# Slave.net
KiCad netlist of a schematic drawn in Altium Designer
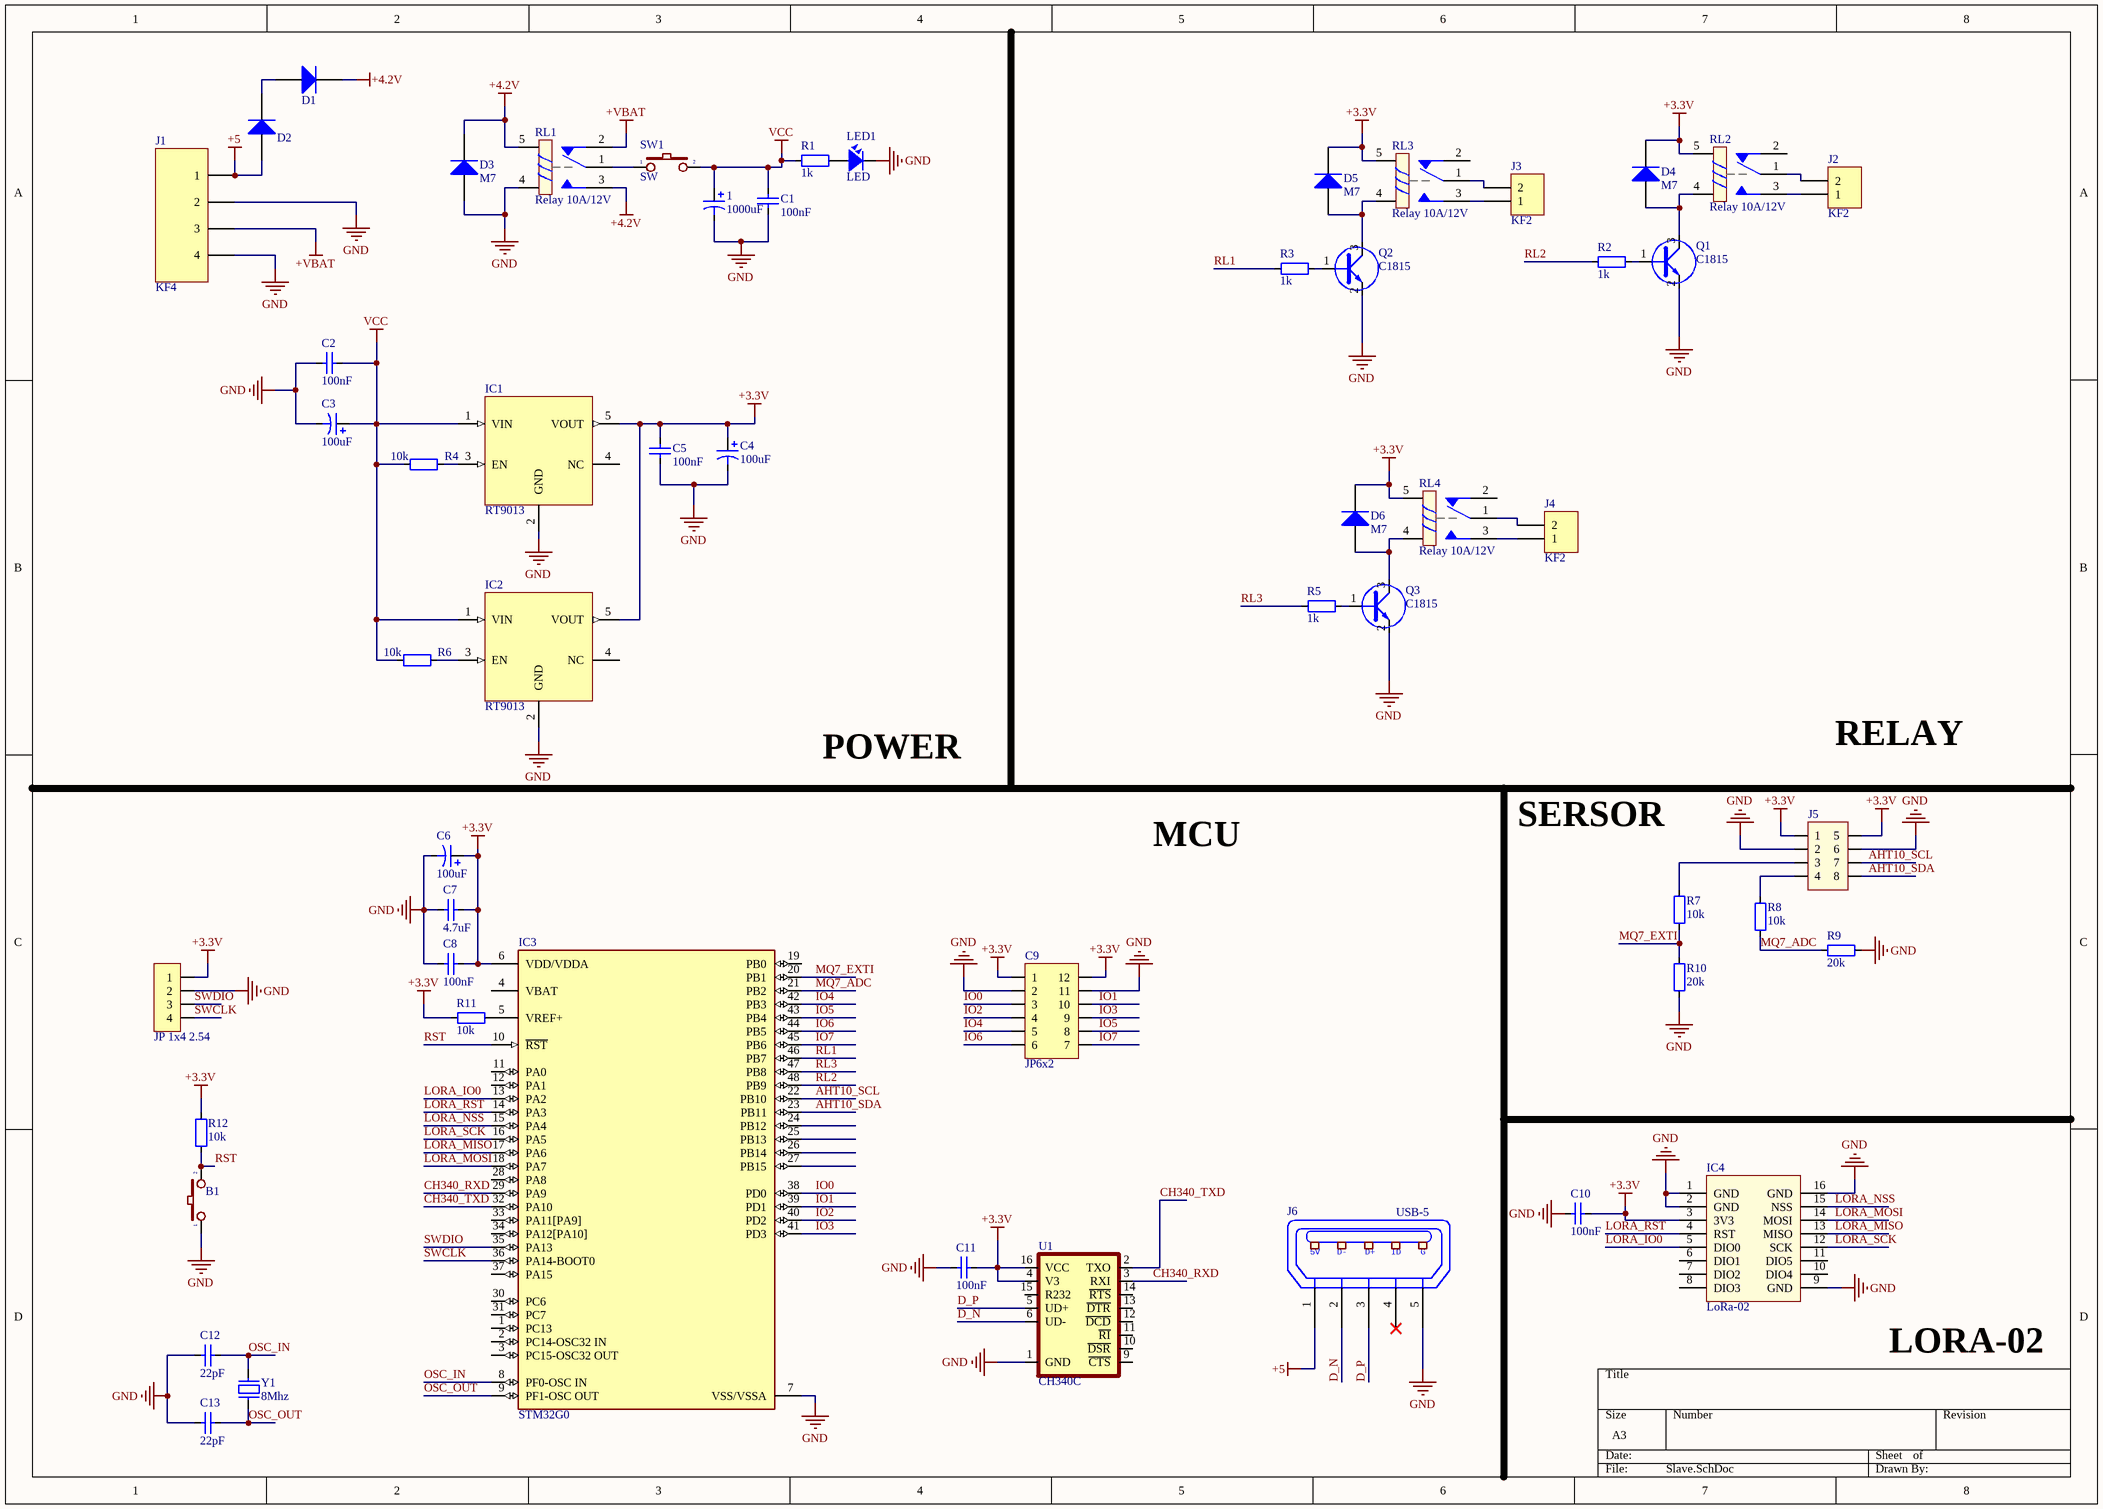
[diagram p0: Slave.SchDoc]

(export (version "E")
  (design (tool "Eeschema 10.0.6"))
  (components
    (comp (ref "1")
      (value "1000uF")
      (footprint "C8mm")
      (description "1000uF 16V 8x16mm")
      (fields (field (name "PUBLISHER") "Altium Limited"))
      (libsource (lib "My Library") (part "Cap Pol"))
    )
    (comp (ref "B1")
      (value "Button 3x4x2.5")
      (footprint "Button 3x4x2.5")
      (libsource (lib "My Library") (part "Button 3x4x2.5"))
    )
    (comp (ref "C1")
      (value "100nF")
      (footprint "CAP_0805")
      (description "Capacitor")
      (fields (field (name "PUBLISHER") "Altium Limited"))
      (libsource (lib "My Library") (part "CapSMD"))
    )
    (comp (ref "C2")
      (value "100nF")
      (footprint "CAP_0805")
      (description "Capacitor")
      (fields (field (name "PUBLISHER") "Altium Limited"))
      (libsource (lib "My Library") (part "CapSMD"))
    )
    (comp (ref "C3")
      (value "100uF")
      (footprint "C5mm")
      (description "100uF 16V")
      (fields (field (name "PUBLISHER") "Altium Limited"))
      (libsource (lib "My Library") (part "Cap Pol"))
    )
    (comp (ref "C4")
      (value "100uF")
      (footprint "C5mm")
      (description "100uF 16V")
      (fields (field (name "PUBLISHER") "Altium Limited"))
      (libsource (lib "My Library") (part "Cap Pol"))
    )
    (comp (ref "C5")
      (value "100nF")
      (footprint "CAP_0805")
      (description "Capacitor")
      (fields (field (name "PUBLISHER") "Altium Limited"))
      (libsource (lib "My Library") (part "CapSMD"))
    )
    (comp (ref "C6")
      (value "100uF")
      (footprint "C5mm")
      (description "100uF 16V")
      (fields (field (name "PUBLISHER") "Altium Limited"))
      (libsource (lib "My Library") (part "Cap Pol"))
    )
    (comp (ref "C7")
      (value "4.7uF")
      (footprint "CAP_0805")
      (description "Capacitor")
      (fields (field (name "PUBLISHER") "Altium Limited"))
      (libsource (lib "My Library") (part "CapSMD"))
    )
    (comp (ref "C8")
      (value "100nF")
      (footprint "CAP_0805")
      (description "Capacitor")
      (fields (field (name "PUBLISHER") "Altium Limited"))
      (libsource (lib "My Library") (part "CapSMD"))
    )
    (comp (ref "C9")
      (value "JP6x2")
      (footprint "JP6-D2T")
      (description "WR-PHD 2.54 mm Dual Socket Header")
      (fields
        (field (name "MANUFACTURER") "Würth Elektronik eiSos GmbH")
        (field (name "PARTNO") "61301221821")
        (field (name "CREATED BY") "Karrer Zheng")
      )
      (libsource (lib "My Library") (part "JP6x2"))
    )
    (comp (ref "C10")
      (value "100nF")
      (footprint "CAP_0805")
      (description "Capacitor")
      (fields (field (name "PUBLISHER") "Altium Limited"))
      (libsource (lib "My Library") (part "CapSMD"))
    )
    (comp (ref "C11")
      (value "100nF")
      (footprint "CAP_0805")
      (description "Capacitor")
      (fields (field (name "PUBLISHER") "Altium Limited"))
      (libsource (lib "My Library") (part "CapSMD"))
    )
    (comp (ref "C12")
      (value "22pF")
      (footprint "CAP_0805")
      (description "Capacitor")
      (fields (field (name "PUBLISHER") "Altium Limited"))
      (libsource (lib "My Library") (part "CapSMD"))
    )
    (comp (ref "C13")
      (value "22pF")
      (footprint "CAP_0805")
      (description "Capacitor")
      (fields (field (name "PUBLISHER") "Altium Limited"))
      (libsource (lib "My Library") (part "CapSMD"))
    )
    (comp (ref "D1")
      (value "SS34 Diode 3A 40V")
      (footprint "DIODE SMA")
      (description "Dán")
      (libsource (lib "Altium_Lib_by_KhueNguyenCreator") (part "Diode M7 ( 4007 )"))
    )
    (comp (ref "D2")
      (value "SS34 Diode 3A 40V")
      (footprint "DIODE SMA")
      (description "Dán")
      (libsource (lib "Altium_Lib_by_KhueNguyenCreator") (part "Diode M7 ( 4007 )"))
    )
    (comp (ref "D3")
      (value "M7")
      (footprint "DIODE SMA")
      (description "Dán")
      (libsource (lib "Altium_Lib_by_KhueNguyenCreator") (part "Diode M7 ( 4007 )"))
    )
    (comp (ref "D4")
      (value "M7")
      (footprint "DIODE SMA")
      (description "Dán")
      (libsource (lib "Altium_Lib_by_KhueNguyenCreator") (part "Diode M7 ( 4007 )"))
    )
    (comp (ref "D5")
      (value "M7")
      (footprint "DIODE SMA")
      (description "Dán")
      (libsource (lib "Altium_Lib_by_KhueNguyenCreator") (part "Diode M7 ( 4007 )"))
    )
    (comp (ref "D6")
      (value "M7")
      (footprint "DIODE SMA")
      (description "Dán")
      (libsource (lib "Altium_Lib_by_KhueNguyenCreator") (part "Diode M7 ( 4007 )"))
    )
    (comp (ref "IC1")
      (value "RT9013")
      (footprint "SOT23-5")
      (description "RT9013-33GB IC REG LINEAR 3.3V 500mA SOT23-5")
      (libsource (lib "My Library") (part "RT9013"))
    )
    (comp (ref "IC2")
      (value "RT9013")
      (footprint "SOT23-5")
      (description "RT9013-33GB IC REG LINEAR 3.3V 500mA SOT23-5")
      (libsource (lib "My Library") (part "RT9013"))
    )
    (comp (ref "IC3") (value "STM32G0") (footprint "STM32G0") (libsource (lib "My Library") (part "STM32G0")))
    (comp (ref "IC4") (value "LoRa-02") (footprint "LoRa-02") (libsource (lib "My Library") (part "LoRa-02")))
    (comp (ref "J1")
      (value "KF4")
      (footprint "KF4-5.08")
      (fields
        (field (name "MANUFACTURER") "Würth Elektronik eiSos GmbH")
        (field (name "PARTNO") "691133710004")
        (field (name "CREATED BY") "Baojun Chen")
      )
      (libsource (lib "My Library") (part "KF4"))
    )
    (comp (ref "J2")
      (value "KF2")
      (footprint "KF2-3.5")
      (fields
        (field (name "MANUFACTURER") "Würth Elektronik eiSos GmbH")
        (field (name "PARTNO") "691103110002")
        (field (name "CREATED BY") "Karrer Zheng")
      )
      (libsource (lib "My Library") (part "KF2"))
    )
    (comp (ref "J3")
      (value "KF2")
      (footprint "KF2-3.5")
      (fields
        (field (name "MANUFACTURER") "Würth Elektronik eiSos GmbH")
        (field (name "PARTNO") "691103110002")
        (field (name "CREATED BY") "Karrer Zheng")
      )
      (libsource (lib "My Library") (part "KF2"))
    )
    (comp (ref "J4")
      (value "KF2")
      (footprint "KF2-3.5")
      (fields
        (field (name "MANUFACTURER") "Würth Elektronik eiSos GmbH")
        (field (name "PARTNO") "691103110002")
        (field (name "CREATED BY") "Karrer Zheng")
      )
      (libsource (lib "My Library") (part "KF2"))
    )
    (comp (ref "J5")
      (value "Connector 4x2")
      (footprint "JP4x2")
      (libsource (lib "My Library") (part "JP4x2"))
    )
    (comp (ref "J6")
      (value "USB-5")
      (footprint "USB-M1")
      (fields
        (field (name "MANUFACTURER") "FCI")
        (field (name "MANUFACTURER PART NUMBER") "10118193-0001LF")
        (field (name ".CREATOR") "MM")
        (field (name ".CHECKED PCB") "RF")
        (field (name ".CHECKED SCH") "MM")
      )
      (libsource (lib "My Library") (part "USB-5"))
    )
    (comp (ref "JP1")
      (value "JP 1x4 2.54")
      (footprint "JP 1x4 DT")
      (description "Cắm")
      (libsource (lib "Altium_Lib_by_KhueNguyenCreator") (part "JP 1x4 2.54 Duc Thang"))
    )
    (comp (ref "LED1")
      (value "LED")
      (footprint "LED-0805-Red")
      (description "LED Single colour Green and Red")
      (libsource (lib "My Library") (part "LED"))
    )
    (comp (ref "Q1")
      (value "C1815")
      (footprint "SOT23D")
      (description "NPN 600mW, ECB")
      (libsource (lib "My Library") (part "2SC1815"))
    )
    (comp (ref "Q2")
      (value "C1815")
      (footprint "SOT23D")
      (description "NPN 600mW, ECB")
      (libsource (lib "My Library") (part "2SC1815"))
    )
    (comp (ref "Q3")
      (value "C1815")
      (footprint "SOT23D")
      (description "NPN 600mW, ECB")
      (libsource (lib "My Library") (part "2SC1815"))
    )
    (comp (ref "R1")
      (value "1k")
      (footprint "RES-SMD-0805")
      (description "Resistor")
      (fields
        (field (name "MANUFACTURER") "Generic Components")
        (field (name "PUBLISHER") "Altium Hobart Technology Centre")
      )
      (libsource (lib "My Library") (part "Resistor - SMD"))
    )
    (comp (ref "R2")
      (value "1k")
      (footprint "RES-SMD-0805")
      (description "Resistor")
      (fields
        (field (name "MANUFACTURER") "Generic Components")
        (field (name "PUBLISHER") "Altium Hobart Technology Centre")
      )
      (libsource (lib "My Library") (part "Resistor - SMD"))
    )
    (comp (ref "R3")
      (value "1k")
      (footprint "RES-SMD-0805")
      (description "Resistor")
      (fields
        (field (name "MANUFACTURER") "Generic Components")
        (field (name "PUBLISHER") "Altium Hobart Technology Centre")
      )
      (libsource (lib "My Library") (part "Resistor - SMD"))
    )
    (comp (ref "R4")
      (value "10k")
      (footprint "RES-SMD-0805")
      (description "Resistor")
      (fields
        (field (name "MANUFACTURER") "Generic Components")
        (field (name "PUBLISHER") "Altium Hobart Technology Centre")
      )
      (libsource (lib "My Library") (part "Resistor - SMD"))
    )
    (comp (ref "R5")
      (value "1k")
      (footprint "RES-SMD-0805")
      (description "Resistor")
      (fields
        (field (name "MANUFACTURER") "Generic Components")
        (field (name "PUBLISHER") "Altium Hobart Technology Centre")
      )
      (libsource (lib "My Library") (part "Resistor - SMD"))
    )
    (comp (ref "R6")
      (value "10k")
      (footprint "RES-SMD-0805")
      (description "Resistor")
      (fields
        (field (name "MANUFACTURER") "Generic Components")
        (field (name "PUBLISHER") "Altium Hobart Technology Centre")
      )
      (libsource (lib "My Library") (part "Resistor - SMD"))
    )
    (comp (ref "R7")
      (value "10k")
      (footprint "RES-SMD-0805")
      (description "Resistor")
      (fields
        (field (name "MANUFACTURER") "Generic Components")
        (field (name "PUBLISHER") "Altium Hobart Technology Centre")
      )
      (libsource (lib "My Library") (part "Resistor - SMD"))
    )
    (comp (ref "R8")
      (value "10k")
      (footprint "RES-SMD-0805")
      (description "Resistor")
      (fields
        (field (name "MANUFACTURER") "Generic Components")
        (field (name "PUBLISHER") "Altium Hobart Technology Centre")
      )
      (libsource (lib "My Library") (part "Resistor - SMD"))
    )
    (comp (ref "R9")
      (value "20k")
      (footprint "RES-SMD-0805")
      (description "Resistor")
      (fields
        (field (name "MANUFACTURER") "Generic Components")
        (field (name "PUBLISHER") "Altium Hobart Technology Centre")
      )
      (libsource (lib "My Library") (part "Resistor - SMD"))
    )
    (comp (ref "R10")
      (value "20k")
      (footprint "RES-SMD-0805")
      (description "Resistor")
      (fields
        (field (name "MANUFACTURER") "Generic Components")
        (field (name "PUBLISHER") "Altium Hobart Technology Centre")
      )
      (libsource (lib "My Library") (part "Resistor - SMD"))
    )
    (comp (ref "R11")
      (value "10k")
      (footprint "RES-SMD-0805")
      (description "Resistor")
      (fields
        (field (name "MANUFACTURER") "Generic Components")
        (field (name "PUBLISHER") "Altium Hobart Technology Centre")
      )
      (libsource (lib "My Library") (part "Resistor - SMD"))
    )
    (comp (ref "R12")
      (value "10k")
      (footprint "RES-SMD-0805")
      (description "Resistor")
      (fields
        (field (name "MANUFACTURER") "Generic Components")
        (field (name "PUBLISHER") "Altium Hobart Technology Centre")
      )
      (libsource (lib "My Library") (part "Resistor - SMD"))
    )
    (comp (ref "RL1")
      (value "Relay 10A/12V")
      (footprint "RELAY 5")
      (description "Relay SPDT,10A - 12VDC 5 Pin")
      (libsource (lib "My Library") (part "Relay 5"))
    )
    (comp (ref "RL2")
      (value "Relay 10A/12V")
      (footprint "RELAY 5")
      (description "Relay SPDT,10A - 12VDC 5 Pin")
      (libsource (lib "My Library") (part "Relay 5"))
    )
    (comp (ref "RL3")
      (value "Relay 10A/12V")
      (footprint "RELAY 5")
      (description "Relay SPDT,10A - 12VDC 5 Pin")
      (libsource (lib "My Library") (part "Relay 5"))
    )
    (comp (ref "RL4")
      (value "Relay 10A/12V")
      (footprint "RELAY 5")
      (description "Relay SPDT,10A - 12VDC 5 Pin")
      (libsource (lib "My Library") (part "Relay 5"))
    )
    (comp (ref "SW1")
      (value "SW")
      (footprint "SW2")
      (description "Switch button 2 pin")
      (libsource (lib "My Library") (part "SW2"))
    )
    (comp (ref "U1")
      (value "CH340C")
      (footprint "SO016")
      (description "USB to serial chip CH340")
      (fields (field (name "MF") "WCH"))
      (libsource (lib "My Library") (part "CH340C"))
    )
    (comp (ref "Y1")
      (value "8Mhz")
      (footprint "Thach Anh 2 chan SMD5032")
      (description "Crystal For all Crystal 2pin.")
      (libsource (lib "Altium_Lib_by_KhueNguyenCreator") (part "Thach Anh 2 chan SMD 5032"))
    )
  )
  (nets
    (net (code "1") (name "+3.3V") (class "Default")
      (node (ref "C10") (pin "2") (pinfunction "2_2") (pintype "passive"))
      (node (ref "C11") (pin "2") (pinfunction "2_2") (pintype "passive"))
      (node (ref "C4") (pin "1") (pinfunction "1_1") (pintype "passive"))
      (node (ref "C5") (pin "1") (pinfunction "1_1") (pintype "passive"))
      (node (ref "C6") (pin "1") (pinfunction "1_1") (pintype "passive"))
      (node (ref "C7") (pin "2") (pinfunction "2_2") (pintype "passive"))
      (node (ref "C8") (pin "1") (pinfunction "1_1") (pintype "passive"))
      (node (ref "C9") (pin "1") (pinfunction "1_1") (pintype "passive"))
      (node (ref "C9") (pin "12") (pinfunction "12_12") (pintype "passive"))
      (node (ref "D4") (pin "2") (pinfunction "K_2") (pintype "passive"))
      (node (ref "D5") (pin "2") (pinfunction "K_2") (pintype "passive"))
      (node (ref "D6") (pin "2") (pinfunction "K_2") (pintype "passive"))
      (node (ref "IC1") (pin "5") (pinfunction "VOUT_5") (pintype "output"))
      (node (ref "IC2") (pin "5") (pinfunction "VOUT_5") (pintype "output"))
      (node (ref "IC3") (pin "6") (pinfunction "VDD/VDDA_6") (pintype "power_in"))
      (node (ref "IC4") (pin "3") (pinfunction "3V3_3") (pintype "passive"))
      (node (ref "J5") (pin "1") (pinfunction "1_1") (pintype "passive"))
      (node (ref "J5") (pin "5") (pinfunction "5_5") (pintype "passive"))
      (node (ref "JP1") (pin "1") (pinfunction "1_1") (pintype "passive"))
      (node (ref "R11") (pin "1") (pinfunction "1_1") (pintype "passive"))
      (node (ref "R12") (pin "1") (pinfunction "1_1") (pintype "passive"))
      (node (ref "RL2") (pin "5") (pinfunction "5_5") (pintype "passive"))
      (node (ref "RL3") (pin "5") (pinfunction "5_5") (pintype "passive"))
      (node (ref "RL4") (pin "5") (pinfunction "5_5") (pintype "passive"))
      (node (ref "U1") (pin "16") (pinfunction "VCC_16") (pintype "bidirectional"))
      (node (ref "U1") (pin "4") (pinfunction "V3_4") (pintype "bidirectional"))
    )
    (net (code "2") (name "+4.2V") (class "Default")
      (node (ref "D1") (pin "2") (pinfunction "K_2") (pintype "passive"))
      (node (ref "D3") (pin "2") (pinfunction "K_2") (pintype "passive"))
      (node (ref "RL1") (pin "3") (pinfunction "3_3") (pintype "passive"))
      (node (ref "RL1") (pin "5") (pinfunction "5_5") (pintype "passive"))
    )
    (net (code "3") (name "+5") (class "Default")
      (node (ref "D2") (pin "1") (pinfunction "A_1") (pintype "passive"))
      (node (ref "J1") (pin "1") (pinfunction "1_1") (pintype "passive"))
      (node (ref "J6") (pin "1") (pinfunction "P1_1") (pintype "passive"))
    )
    (net (code "4") (name "+VBAT") (class "Default")
      (node (ref "J1") (pin "3") (pinfunction "3_3") (pintype "passive"))
      (node (ref "RL1") (pin "2") (pinfunction "2_2") (pintype "passive"))
    )
    (net (code "5") (name "/AHT10_SCL") (class "Default")
      (node (ref "IC3") (pin "22") (pinfunction "PB10_22") (pintype "bidirectional"))
      (node (ref "J5") (pin "7") (pinfunction "7_7") (pintype "passive"))
    )
    (net (code "6") (name "/AHT10_SDA") (class "Default")
      (node (ref "IC3") (pin "23") (pinfunction "PB11_23") (pintype "bidirectional"))
      (node (ref "J5") (pin "8") (pinfunction "8_8") (pintype "passive"))
    )
    (net (code "7") (name "/CH340_RXD") (class "Default")
      (node (ref "IC3") (pin "29") (pinfunction "PA9_29") (pintype "bidirectional"))
      (node (ref "U1") (pin "3") (pinfunction "RXI_3") (pintype "bidirectional"))
    )
    (net (code "8") (name "/CH340_TXD") (class "Default")
      (node (ref "IC3") (pin "32") (pinfunction "PA10_32") (pintype "bidirectional"))
      (node (ref "U1") (pin "2") (pinfunction "TXO_2") (pintype "bidirectional"))
    )
    (net (code "9") (name "/D_N") (class "Default")
      (node (ref "J6") (pin "2") (pinfunction "P2_2") (pintype "passive"))
      (node (ref "U1") (pin "6") (pinfunction "UD-_6") (pintype "bidirectional"))
    )
    (net (code "10") (name "/D_P") (class "Default")
      (node (ref "J6") (pin "3") (pinfunction "P3_3") (pintype "passive"))
      (node (ref "U1") (pin "5") (pinfunction "UD+_5") (pintype "bidirectional"))
    )
    (net (code "11") (name "/IO0") (class "Default")
      (node (ref "C9") (pin "3") (pinfunction "3_3") (pintype "passive"))
      (node (ref "IC3") (pin "38") (pinfunction "PD0_38") (pintype "bidirectional"))
    )
    (net (code "12") (name "/IO1") (class "Default")
      (node (ref "C9") (pin "10") (pinfunction "10_10") (pintype "passive"))
      (node (ref "IC3") (pin "39") (pinfunction "PD1_39") (pintype "bidirectional"))
    )
    (net (code "13") (name "/IO2") (class "Default")
      (node (ref "C9") (pin "4") (pinfunction "4_4") (pintype "passive"))
      (node (ref "IC3") (pin "40") (pinfunction "PD2_40") (pintype "bidirectional"))
    )
    (net (code "14") (name "/IO3") (class "Default")
      (node (ref "C9") (pin "9") (pinfunction "9_9") (pintype "passive"))
      (node (ref "IC3") (pin "41") (pinfunction "PD3_41") (pintype "bidirectional"))
    )
    (net (code "15") (name "/IO4") (class "Default")
      (node (ref "C9") (pin "5") (pinfunction "5_5") (pintype "passive"))
      (node (ref "IC3") (pin "42") (pinfunction "PB3_42") (pintype "bidirectional"))
    )
    (net (code "16") (name "/IO5") (class "Default")
      (node (ref "C9") (pin "8") (pinfunction "8_8") (pintype "passive"))
      (node (ref "IC3") (pin "43") (pinfunction "PB4_43") (pintype "bidirectional"))
    )
    (net (code "17") (name "/IO6") (class "Default")
      (node (ref "C9") (pin "6") (pinfunction "6_6") (pintype "passive"))
      (node (ref "IC3") (pin "44") (pinfunction "PB5_44") (pintype "bidirectional"))
    )
    (net (code "18") (name "/IO7") (class "Default")
      (node (ref "C9") (pin "7") (pinfunction "7_7") (pintype "passive"))
      (node (ref "IC3") (pin "45") (pinfunction "PB6_45") (pintype "bidirectional"))
    )
    (net (code "19") (name "/LORA_IO0") (class "Default")
      (node (ref "IC3") (pin "13") (pinfunction "PA2_13") (pintype "bidirectional"))
      (node (ref "IC4") (pin "5") (pinfunction "DIO0_5") (pintype "passive"))
    )
    (net (code "20") (name "/LORA_MISO") (class "Default")
      (node (ref "IC3") (pin "17") (pinfunction "PA6_17") (pintype "bidirectional"))
      (node (ref "IC4") (pin "13") (pinfunction "MISO_13") (pintype "passive"))
    )
    (net (code "21") (name "/LORA_MOSI") (class "Default")
      (node (ref "IC3") (pin "18") (pinfunction "PA7_18") (pintype "bidirectional"))
      (node (ref "IC4") (pin "14") (pinfunction "MOSI_14") (pintype "passive"))
    )
    (net (code "22") (name "/LORA_NSS") (class "Default")
      (node (ref "IC3") (pin "15") (pinfunction "PA4_15") (pintype "bidirectional"))
      (node (ref "IC4") (pin "15") (pinfunction "NSS_15") (pintype "passive"))
    )
    (net (code "23") (name "/LORA_RST") (class "Default")
      (node (ref "IC3") (pin "14") (pinfunction "PA3_14") (pintype "bidirectional"))
      (node (ref "IC4") (pin "4") (pinfunction "RST_4") (pintype "passive"))
    )
    (net (code "24") (name "/LORA_SCK") (class "Default")
      (node (ref "IC3") (pin "16") (pinfunction "PA5_16") (pintype "bidirectional"))
      (node (ref "IC4") (pin "12") (pinfunction "SCK_12") (pintype "passive"))
    )
    (net (code "25") (name "/MQ7_ADC") (class "Default")
      (node (ref "IC3") (pin "21") (pinfunction "PB2_21") (pintype "bidirectional"))
      (node (ref "R8") (pin "1") (pinfunction "1_1") (pintype "passive"))
      (node (ref "R9") (pin "2") (pinfunction "2_2") (pintype "passive"))
    )
    (net (code "26") (name "/MQ7_EXTI") (class "Default")
      (node (ref "IC3") (pin "20") (pinfunction "PB1_20") (pintype "bidirectional"))
      (node (ref "R10") (pin "2") (pinfunction "2_2") (pintype "passive"))
      (node (ref "R7") (pin "1") (pinfunction "1_1") (pintype "passive"))
    )
    (net (code "27") (name "/OSC_IN") (class "Default")
      (node (ref "C12") (pin "1") (pinfunction "1_1") (pintype "passive"))
      (node (ref "IC3") (pin "8") (pinfunction "PF0-OSC_IN_8") (pintype "bidirectional"))
      (node (ref "Y1") (pin "2") (pinfunction "2_2") (pintype "passive"))
    )
    (net (code "28") (name "/OSC_OUT") (class "Default")
      (node (ref "C13") (pin "1") (pinfunction "1_1") (pintype "passive"))
      (node (ref "IC3") (pin "9") (pinfunction "PF1-OSC_OUT_9") (pintype "bidirectional"))
      (node (ref "Y1") (pin "1") (pinfunction "1_1") (pintype "passive"))
    )
    (net (code "29") (name "/RL1") (class "Default")
      (node (ref "IC3") (pin "46") (pinfunction "PB7_46") (pintype "bidirectional"))
      (node (ref "R3") (pin "1") (pinfunction "1_1") (pintype "passive"))
    )
    (net (code "30") (name "/RL2") (class "Default")
      (node (ref "IC3") (pin "48") (pinfunction "PB9_48") (pintype "bidirectional"))
      (node (ref "R2") (pin "1") (pinfunction "1_1") (pintype "passive"))
    )
    (net (code "31") (name "/RL3") (class "Default")
      (node (ref "IC3") (pin "47") (pinfunction "PB8_47") (pintype "bidirectional"))
      (node (ref "R5") (pin "1") (pinfunction "1_1") (pintype "passive"))
    )
    (net (code "32") (name "/RST") (class "Default")
      (node (ref "B1") (pin "2") (pinfunction "2_2") (pintype "passive"))
      (node (ref "IC3") (pin "10") (pinfunction "~{RST}_10") (pintype "input"))
      (node (ref "R12") (pin "2") (pinfunction "2_2") (pintype "passive"))
    )
    (net (code "33") (name "/SWCLK") (class "Default")
      (node (ref "IC3") (pin "36") (pinfunction "PA14-BOOT0_36") (pintype "bidirectional"))
      (node (ref "JP1") (pin "4") (pinfunction "4_4") (pintype "passive"))
    )
    (net (code "34") (name "/SWDIO") (class "Default")
      (node (ref "IC3") (pin "35") (pinfunction "PA13_35") (pintype "bidirectional"))
      (node (ref "JP1") (pin "3") (pinfunction "3_3") (pintype "passive"))
    )
    (net (code "35") (name "GND") (class "Default")
      (node (ref "1") (pin "2") (pinfunction "2_2") (pintype "passive"))
      (node (ref "B1") (pin "1") (pinfunction "1_1") (pintype "passive"))
      (node (ref "C1") (pin "2") (pinfunction "2_2") (pintype "passive"))
      (node (ref "C10") (pin "1") (pinfunction "1_1") (pintype "passive"))
      (node (ref "C11") (pin "1") (pinfunction "1_1") (pintype "passive"))
      (node (ref "C12") (pin "2") (pinfunction "2_2") (pintype "passive"))
      (node (ref "C13") (pin "2") (pinfunction "2_2") (pintype "passive"))
      (node (ref "C2") (pin "2") (pinfunction "2_2") (pintype "passive"))
      (node (ref "C3") (pin "2") (pinfunction "2_2") (pintype "passive"))
      (node (ref "C4") (pin "2") (pinfunction "2_2") (pintype "passive"))
      (node (ref "C5") (pin "2") (pinfunction "2_2") (pintype "passive"))
      (node (ref "C6") (pin "2") (pinfunction "2_2") (pintype "passive"))
      (node (ref "C7") (pin "1") (pinfunction "1_1") (pintype "passive"))
      (node (ref "C8") (pin "2") (pinfunction "2_2") (pintype "passive"))
      (node (ref "C9") (pin "11") (pinfunction "11_11") (pintype "passive"))
      (node (ref "C9") (pin "2") (pinfunction "2_2") (pintype "passive"))
      (node (ref "D3") (pin "1") (pinfunction "A_1") (pintype "passive"))
      (node (ref "IC1") (pin "2") (pinfunction "GND_2") (pintype "passive"))
      (node (ref "IC2") (pin "2") (pinfunction "GND_2") (pintype "passive"))
      (node (ref "IC3") (pin "7") (pinfunction "VSS/VSSA_7") (pintype "power_in"))
      (node (ref "IC4") (pin "1") (pinfunction "GND_1") (pintype "passive"))
      (node (ref "IC4") (pin "16") (pinfunction "GND_16") (pintype "passive"))
      (node (ref "IC4") (pin "2") (pinfunction "GND_2") (pintype "passive"))
      (node (ref "IC4") (pin "9") (pinfunction "GND_9") (pintype "passive"))
      (node (ref "J1") (pin "2") (pinfunction "2_2") (pintype "passive"))
      (node (ref "J1") (pin "4") (pinfunction "4_4") (pintype "passive"))
      (node (ref "J5") (pin "2") (pinfunction "2_2") (pintype "passive"))
      (node (ref "J5") (pin "6") (pinfunction "6_6") (pintype "passive"))
      (node (ref "J6") (pin "5") (pinfunction "P5_5") (pintype "passive"))
      (node (ref "JP1") (pin "2") (pinfunction "2_2") (pintype "passive"))
      (node (ref "LED1") (pin "2") (pinfunction "2_2") (pintype "passive"))
      (node (ref "Q1") (pin "2") (pinfunction "E_2") (pintype "passive"))
      (node (ref "Q2") (pin "2") (pinfunction "E_2") (pintype "passive"))
      (node (ref "Q3") (pin "2") (pinfunction "E_2") (pintype "passive"))
      (node (ref "R10") (pin "1") (pinfunction "1_1") (pintype "passive"))
      (node (ref "R9") (pin "1") (pinfunction "1_1") (pintype "passive"))
      (node (ref "RL1") (pin "4") (pinfunction "4_4") (pintype "passive"))
      (node (ref "U1") (pin "1") (pinfunction "GND_1") (pintype "bidirectional"))
    )
    (net (code "36") (name "Net-(D1-A)") (class "Default")
      (node (ref "D1") (pin "1") (pinfunction "A_1") (pintype "passive"))
      (node (ref "D2") (pin "2") (pinfunction "K_2") (pintype "passive"))
    )
    (net (code "37") (name "Net-(D4-A)") (class "Default")
      (node (ref "D4") (pin "1") (pinfunction "A_1") (pintype "passive"))
      (node (ref "Q1") (pin "3") (pinfunction "C_3") (pintype "passive"))
      (node (ref "RL2") (pin "4") (pinfunction "4_4") (pintype "passive"))
    )
    (net (code "38") (name "Net-(D5-A)") (class "Default")
      (node (ref "D5") (pin "1") (pinfunction "A_1") (pintype "passive"))
      (node (ref "Q2") (pin "3") (pinfunction "C_3") (pintype "passive"))
      (node (ref "RL3") (pin "4") (pinfunction "4_4") (pintype "passive"))
    )
    (net (code "39") (name "Net-(D6-A)") (class "Default")
      (node (ref "D6") (pin "1") (pinfunction "A_1") (pintype "passive"))
      (node (ref "Q3") (pin "3") (pinfunction "C_3") (pintype "passive"))
      (node (ref "RL4") (pin "4") (pinfunction "4_4") (pintype "passive"))
    )
    (net (code "40") (name "Net-(IC1-EN)") (class "Default")
      (node (ref "IC1") (pin "3") (pinfunction "EN_3") (pintype "input"))
      (node (ref "R4") (pin "1") (pinfunction "1_1") (pintype "passive"))
    )
    (net (code "41") (name "Net-(IC2-EN)") (class "Default")
      (node (ref "IC2") (pin "3") (pinfunction "EN_3") (pintype "input"))
      (node (ref "R6") (pin "1") (pinfunction "1_1") (pintype "passive"))
    )
    (net (code "42") (name "Net-(IC3-VREF+)") (class "Default")
      (node (ref "IC3") (pin "5") (pinfunction "VREF+_5") (pintype "power_in"))
      (node (ref "R11") (pin "2") (pinfunction "2_2") (pintype "passive"))
    )
    (net (code "43") (name "Net-(J2-Pad1)") (class "Default")
      (node (ref "J2") (pin "1") (pinfunction "1_1") (pintype "passive"))
      (node (ref "RL2") (pin "3") (pinfunction "3_3") (pintype "passive"))
    )
    (net (code "44") (name "Net-(J2-Pad2)") (class "Default")
      (node (ref "J2") (pin "2") (pinfunction "2_2") (pintype "passive"))
      (node (ref "RL2") (pin "1") (pinfunction "1_1") (pintype "passive"))
    )
    (net (code "45") (name "Net-(J3-Pad1)") (class "Default")
      (node (ref "J3") (pin "1") (pinfunction "1_1") (pintype "passive"))
      (node (ref "RL3") (pin "3") (pinfunction "3_3") (pintype "passive"))
    )
    (net (code "46") (name "Net-(J3-Pad2)") (class "Default")
      (node (ref "J3") (pin "2") (pinfunction "2_2") (pintype "passive"))
      (node (ref "RL3") (pin "1") (pinfunction "1_1") (pintype "passive"))
    )
    (net (code "47") (name "Net-(J4-Pad1)") (class "Default")
      (node (ref "J4") (pin "1") (pinfunction "1_1") (pintype "passive"))
      (node (ref "RL4") (pin "3") (pinfunction "3_3") (pintype "passive"))
    )
    (net (code "48") (name "Net-(J4-Pad2)") (class "Default")
      (node (ref "J4") (pin "2") (pinfunction "2_2") (pintype "passive"))
      (node (ref "RL4") (pin "1") (pinfunction "1_1") (pintype "passive"))
    )
    (net (code "49") (name "Net-(J5-Pad3)") (class "Default")
      (node (ref "J5") (pin "3") (pinfunction "3_3") (pintype "passive"))
      (node (ref "R7") (pin "2") (pinfunction "2_2") (pintype "passive"))
    )
    (net (code "50") (name "Net-(J5-Pad4)") (class "Default")
      (node (ref "J5") (pin "4") (pinfunction "4_4") (pintype "passive"))
      (node (ref "R8") (pin "2") (pinfunction "2_2") (pintype "passive"))
    )
    (net (code "51") (name "Net-(LED1-Pad1)") (class "Default")
      (node (ref "LED1") (pin "1") (pinfunction "1_1") (pintype "passive"))
      (node (ref "R1") (pin "1") (pinfunction "1_1") (pintype "passive"))
    )
    (net (code "52") (name "Net-(Q1-B)") (class "Default")
      (node (ref "Q1") (pin "1") (pinfunction "B_1") (pintype "passive"))
      (node (ref "R2") (pin "2") (pinfunction "2_2") (pintype "passive"))
    )
    (net (code "53") (name "Net-(Q2-B)") (class "Default")
      (node (ref "Q2") (pin "1") (pinfunction "B_1") (pintype "passive"))
      (node (ref "R3") (pin "2") (pinfunction "2_2") (pintype "passive"))
    )
    (net (code "54") (name "Net-(Q3-B)") (class "Default")
      (node (ref "Q3") (pin "1") (pinfunction "B_1") (pintype "passive"))
      (node (ref "R5") (pin "2") (pinfunction "2_2") (pintype "passive"))
    )
    (net (code "55") (name "Net-(RL1-Pad1)") (class "Default")
      (node (ref "RL1") (pin "1") (pinfunction "1_1") (pintype "passive"))
      (node (ref "SW1") (pin "1") (pinfunction "1_1") (pintype "passive"))
    )
    (net (code "56") (name "VCC") (class "Default")
      (node (ref "1") (pin "1") (pinfunction "1_1") (pintype "passive"))
      (node (ref "C1") (pin "1") (pinfunction "1_1") (pintype "passive"))
      (node (ref "C2") (pin "1") (pinfunction "1_1") (pintype "passive"))
      (node (ref "C3") (pin "1") (pinfunction "1_1") (pintype "passive"))
      (node (ref "IC1") (pin "1") (pinfunction "VIN_1") (pintype "input"))
      (node (ref "IC2") (pin "1") (pinfunction "VIN_1") (pintype "input"))
      (node (ref "R1") (pin "2") (pinfunction "2_2") (pintype "passive"))
      (node (ref "R4") (pin "2") (pinfunction "2_2") (pintype "passive"))
      (node (ref "R6") (pin "2") (pinfunction "2_2") (pintype "passive"))
      (node (ref "SW1") (pin "2") (pinfunction "2_2") (pintype "passive"))
    )
    (net (code "57") (name "unconnected-(IC1-NC-Pad4)") (class "Default")
      (node (ref "IC1") (pin "4") (pinfunction "NC_4") (pintype "passive"))
    )
    (net (code "58") (name "unconnected-(IC2-NC-Pad4)") (class "Default")
      (node (ref "IC2") (pin "4") (pinfunction "NC_4") (pintype "passive"))
    )
    (net (code "59") (name "unconnected-(IC3-PA0-Pad11)") (class "Default")
      (node (ref "IC3") (pin "11") (pinfunction "PA0_11") (pintype "bidirectional"))
    )
    (net (code "60") (name "unconnected-(IC3-PA1-Pad12)") (class "Default")
      (node (ref "IC3") (pin "12") (pinfunction "PA1_12") (pintype "bidirectional"))
    )
    (net (code "61") (name "unconnected-(IC3-PA8-Pad28)") (class "Default")
      (node (ref "IC3") (pin "28") (pinfunction "PA8_28") (pintype "bidirectional"))
    )
    (net (code "62") (name "unconnected-(IC3-PA11[PA9]-Pad33)") (class "Default")
      (node (ref "IC3") (pin "33") (pinfunction "PA11[PA9]_33") (pintype "bidirectional"))
    )
    (net (code "63") (name "unconnected-(IC3-PA12[PA10]-Pad34)") (class "Default")
      (node (ref "IC3") (pin "34") (pinfunction "PA12[PA10]_34") (pintype "bidirectional"))
    )
    (net (code "64") (name "unconnected-(IC3-PA15-Pad37)") (class "Default")
      (node (ref "IC3") (pin "37") (pinfunction "PA15_37") (pintype "bidirectional"))
    )
    (net (code "65") (name "unconnected-(IC3-PB0-Pad19)") (class "Default")
      (node (ref "IC3") (pin "19") (pinfunction "PB0_19") (pintype "bidirectional"))
    )
    (net (code "66") (name "unconnected-(IC3-PB12-Pad24)") (class "Default")
      (node (ref "IC3") (pin "24") (pinfunction "PB12_24") (pintype "bidirectional"))
    )
    (net (code "67") (name "unconnected-(IC3-PB13-Pad25)") (class "Default")
      (node (ref "IC3") (pin "25") (pinfunction "PB13_25") (pintype "bidirectional"))
    )
    (net (code "68") (name "unconnected-(IC3-PB14-Pad26)") (class "Default")
      (node (ref "IC3") (pin "26") (pinfunction "PB14_26") (pintype "bidirectional"))
    )
    (net (code "69") (name "unconnected-(IC3-PB15-Pad27)") (class "Default")
      (node (ref "IC3") (pin "27") (pinfunction "PB15_27") (pintype "bidirectional"))
    )
    (net (code "70") (name "unconnected-(IC3-PC6-Pad30)") (class "Default")
      (node (ref "IC3") (pin "30") (pinfunction "PC6_30") (pintype "bidirectional"))
    )
    (net (code "71") (name "unconnected-(IC3-PC7-Pad31)") (class "Default")
      (node (ref "IC3") (pin "31") (pinfunction "PC7_31") (pintype "bidirectional"))
    )
    (net (code "72") (name "unconnected-(IC3-PC13-Pad1)") (class "Default")
      (node (ref "IC3") (pin "1") (pinfunction "PC13_1") (pintype "bidirectional"))
    )
    (net (code "73") (name "unconnected-(IC3-PC14-OSC32_IN-Pad2)") (class "Default")
      (node (ref "IC3") (pin "2") (pinfunction "PC14-OSC32_IN_2") (pintype "bidirectional"))
    )
    (net (code "74") (name "unconnected-(IC3-PC15-OSC32_OUT-Pad3)") (class "Default")
      (node (ref "IC3") (pin "3") (pinfunction "PC15-OSC32_OUT_3") (pintype "bidirectional"))
    )
    (net (code "75") (name "unconnected-(IC3-VBAT-Pad4)") (class "Default")
      (node (ref "IC3") (pin "4") (pinfunction "VBAT_4") (pintype "power_in"))
    )
    (net (code "76") (name "unconnected-(IC4-DIO1-Pad6)") (class "Default")
      (node (ref "IC4") (pin "6") (pinfunction "DIO1_6") (pintype "passive"))
    )
    (net (code "77") (name "unconnected-(IC4-DIO2-Pad7)") (class "Default")
      (node (ref "IC4") (pin "7") (pinfunction "DIO2_7") (pintype "passive"))
    )
    (net (code "78") (name "unconnected-(IC4-DIO3-Pad8)") (class "Default")
      (node (ref "IC4") (pin "8") (pinfunction "DIO3_8") (pintype "passive"))
    )
    (net (code "79") (name "unconnected-(IC4-DIO4-Pad10)") (class "Default")
      (node (ref "IC4") (pin "10") (pinfunction "DIO4_10") (pintype "passive"))
    )
    (net (code "80") (name "unconnected-(IC4-DIO5-Pad11)") (class "Default")
      (node (ref "IC4") (pin "11") (pinfunction "DIO5_11") (pintype "passive"))
    )
    (net (code "81") (name "unconnected-(J6-P4-Pad4)") (class "Default")
      (node (ref "J6") (pin "4") (pinfunction "P4_4") (pintype "passive+no_connect"))
    )
    (net (code "82") (name "unconnected-(RL2-Pad2)") (class "Default")
      (node (ref "RL2") (pin "2") (pinfunction "2_2") (pintype "passive"))
    )
    (net (code "83") (name "unconnected-(RL3-Pad2)") (class "Default")
      (node (ref "RL3") (pin "2") (pinfunction "2_2") (pintype "passive"))
    )
    (net (code "84") (name "unconnected-(RL4-Pad2)") (class "Default")
      (node (ref "RL4") (pin "2") (pinfunction "2_2") (pintype "passive"))
    )
    (net (code "85") (name "unconnected-(U1-R232-Pad15)") (class "Default")
      (node (ref "U1") (pin "15") (pinfunction "R232_15") (pintype "bidirectional"))
    )
    (net (code "86") (name "unconnected-(U1-~{CTS}-Pad9)") (class "Default")
      (node (ref "U1") (pin "9") (pinfunction "~{CTS}_9") (pintype "bidirectional"))
    )
    (net (code "87") (name "unconnected-(U1-~{DCD}-Pad12)") (class "Default")
      (node (ref "U1") (pin "12") (pinfunction "~{DCD}_12") (pintype "bidirectional"))
    )
    (net (code "88") (name "unconnected-(U1-~{DSR}-Pad10)") (class "Default")
      (node (ref "U1") (pin "10") (pinfunction "~{DSR}_10") (pintype "bidirectional"))
    )
    (net (code "89") (name "unconnected-(U1-~{DTR}-Pad13)") (class "Default")
      (node (ref "U1") (pin "13") (pinfunction "~{DTR}_13") (pintype "bidirectional"))
    )
    (net (code "90") (name "unconnected-(U1-~{RI}-Pad11)") (class "Default")
      (node (ref "U1") (pin "11") (pinfunction "~{RI}_11") (pintype "bidirectional"))
    )
    (net (code "91") (name "unconnected-(U1-~{RTS}-Pad14)") (class "Default")
      (node (ref "U1") (pin "14") (pinfunction "~{RTS}_14") (pintype "bidirectional"))
    )
  )
)
